# RTC_Block.net
KiCad netlist of a schematic drawn in Altium Designer
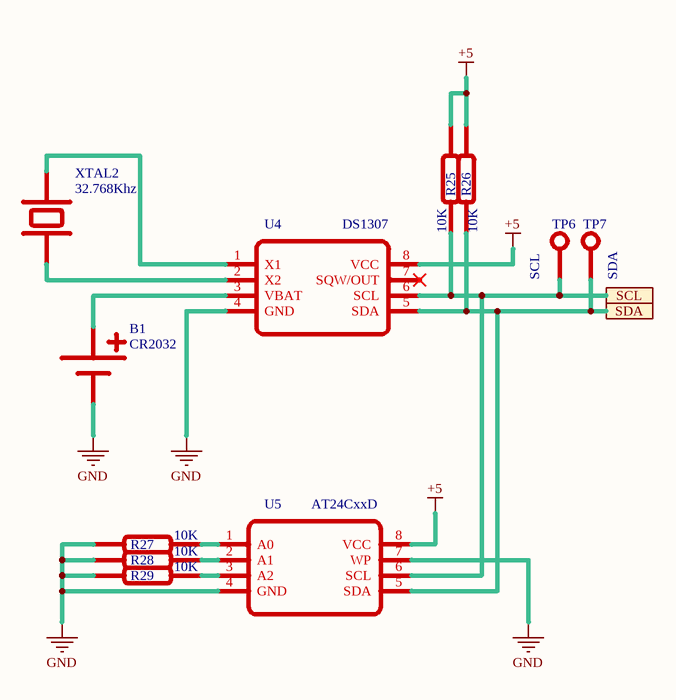
[diagram p0: RTC_Block.SchDoc]

(export (version "E")
  (design (tool "Eeschema 10.0.6"))
  (components
    (comp (ref "B1")
      (value "CR2032")
      (footprint "CR2032-SMD-Thick")
      (description "CR2032 Battery")
      (libsource (lib "CTAI-Library") (part "CR2032"))
    )
    (comp (ref "R25")
      (value "10K")
      (footprint "R0603")
      (description "Resistor")
      (libsource (lib "CTAI-Library") (part "Resistor"))
    )
    (comp (ref "R26")
      (value "10K")
      (footprint "R0603")
      (description "Resistor")
      (libsource (lib "CTAI-Library") (part "Resistor"))
    )
    (comp (ref "R27")
      (value "10K")
      (footprint "R0603")
      (description "Resistor")
      (libsource (lib "CTAI-Library") (part "Resistor"))
    )
    (comp (ref "R28")
      (value "10K")
      (footprint "R0603")
      (description "Resistor")
      (libsource (lib "CTAI-Library") (part "Resistor"))
    )
    (comp (ref "R29")
      (value "10K")
      (footprint "R0603")
      (description "Resistor")
      (libsource (lib "CTAI-Library") (part "Resistor"))
    )
    (comp (ref "TP6")
      (value "SCL")
      (footprint "Test Point")
      (description "Test Point")
      (libsource (lib "CTAI-Library") (part "TestPoint"))
    )
    (comp (ref "TP7")
      (value "SDA")
      (footprint "Test Point")
      (description "Test Point")
      (libsource (lib "CTAI-Library") (part "TestPoint"))
    )
    (comp (ref "U4")
      (value "DS1307")
      (footprint "SOIC8")
      (description "Realtime Clock IC")
      (libsource (lib "CTAI-Library") (part "DS1307"))
    )
    (comp (ref "U5")
      (value "AT24CxxD")
      (footprint "SOIC8")
      (description "I2C Serial EEPROM")
      (libsource (lib "CTAI-Library") (part "AT24CxxD"))
    )
    (comp (ref "XTAL2")
      (value "32.768Khz")
      (footprint "CRYSTAL DT38")
      (description "Crystall 2Pin Capacitor Intergrated")
      (libsource (lib "CTAI-Library") (part "CRYSTAL-2P"))
    )
  )
  (nets
    (net (code "1") (name "+5") (class "Default")
      (node (ref "R25") (pin "2") (pinfunction "2_2") (pintype "passive"))
      (node (ref "R26") (pin "2") (pinfunction "2_2") (pintype "passive"))
      (node (ref "U4") (pin "8") (pinfunction "VCC_8") (pintype "passive"))
      (node (ref "U5") (pin "8") (pinfunction "VCC_8") (pintype "passive"))
    )
    (net (code "2") (name "/SCL") (class "Default")
      (node (ref "R25") (pin "1") (pinfunction "1_1") (pintype "passive"))
      (node (ref "TP6") (pin "1") (pinfunction "1_1") (pintype "passive"))
      (node (ref "U4") (pin "6") (pinfunction "SCL_6") (pintype "passive"))
      (node (ref "U5") (pin "6") (pinfunction "SCL_6") (pintype "passive"))
    )
    (net (code "3") (name "/SDA") (class "Default")
      (node (ref "R26") (pin "1") (pinfunction "1_1") (pintype "passive"))
      (node (ref "TP7") (pin "1") (pinfunction "1_1") (pintype "passive"))
      (node (ref "U4") (pin "5") (pinfunction "SDA_5") (pintype "passive"))
      (node (ref "U5") (pin "5") (pinfunction "SDA_5") (pintype "passive"))
    )
    (net (code "4") (name "GND") (class "Default")
      (node (ref "B1") (pin "2") (pinfunction "2_2") (pintype "passive"))
      (node (ref "R27") (pin "1") (pinfunction "1_1") (pintype "passive"))
      (node (ref "R28") (pin "1") (pinfunction "1_1") (pintype "passive"))
      (node (ref "R29") (pin "1") (pinfunction "1_1") (pintype "passive"))
      (node (ref "U4") (pin "4") (pinfunction "GND_4") (pintype "passive"))
      (node (ref "U5") (pin "4") (pinfunction "GND_4") (pintype "passive"))
      (node (ref "U5") (pin "7") (pinfunction "WP_7") (pintype "passive"))
    )
    (net (code "5") (name "Net-(U4-VBAT)") (class "Default")
      (node (ref "B1") (pin "1") (pinfunction "1_1") (pintype "passive"))
      (node (ref "U4") (pin "3") (pinfunction "VBAT_3") (pintype "passive"))
    )
    (net (code "6") (name "Net-(U4-X1)") (class "Default")
      (node (ref "U4") (pin "1") (pinfunction "X1_1") (pintype "passive"))
      (node (ref "XTAL2") (pin "1") (pinfunction "1_1") (pintype "passive"))
    )
    (net (code "7") (name "Net-(U4-X2)") (class "Default")
      (node (ref "U4") (pin "2") (pinfunction "X2_2") (pintype "passive"))
      (node (ref "XTAL2") (pin "2") (pinfunction "2_2") (pintype "passive"))
    )
    (net (code "8") (name "Net-(U5-A0)") (class "Default")
      (node (ref "R27") (pin "2") (pinfunction "2_2") (pintype "passive"))
      (node (ref "U5") (pin "1") (pinfunction "A0_1") (pintype "output"))
    )
    (net (code "9") (name "Net-(U5-A1)") (class "Default")
      (node (ref "R28") (pin "2") (pinfunction "2_2") (pintype "passive"))
      (node (ref "U5") (pin "2") (pinfunction "A1_2") (pintype "passive"))
    )
    (net (code "10") (name "Net-(U5-A2)") (class "Default")
      (node (ref "R29") (pin "2") (pinfunction "2_2") (pintype "passive"))
      (node (ref "U5") (pin "3") (pinfunction "A2_3") (pintype "passive"))
    )
    (net (code "11") (name "unconnected-(U4-SQW{slash}OUT-Pad7)") (class "Default")
      (node (ref "U4") (pin "7") (pinfunction "SQW/OUT_7") (pintype "output+no_connect"))
    )
  )
)
